# eeZeeRGB.net
KiCad netlist of a schematic drawn in EAGLE
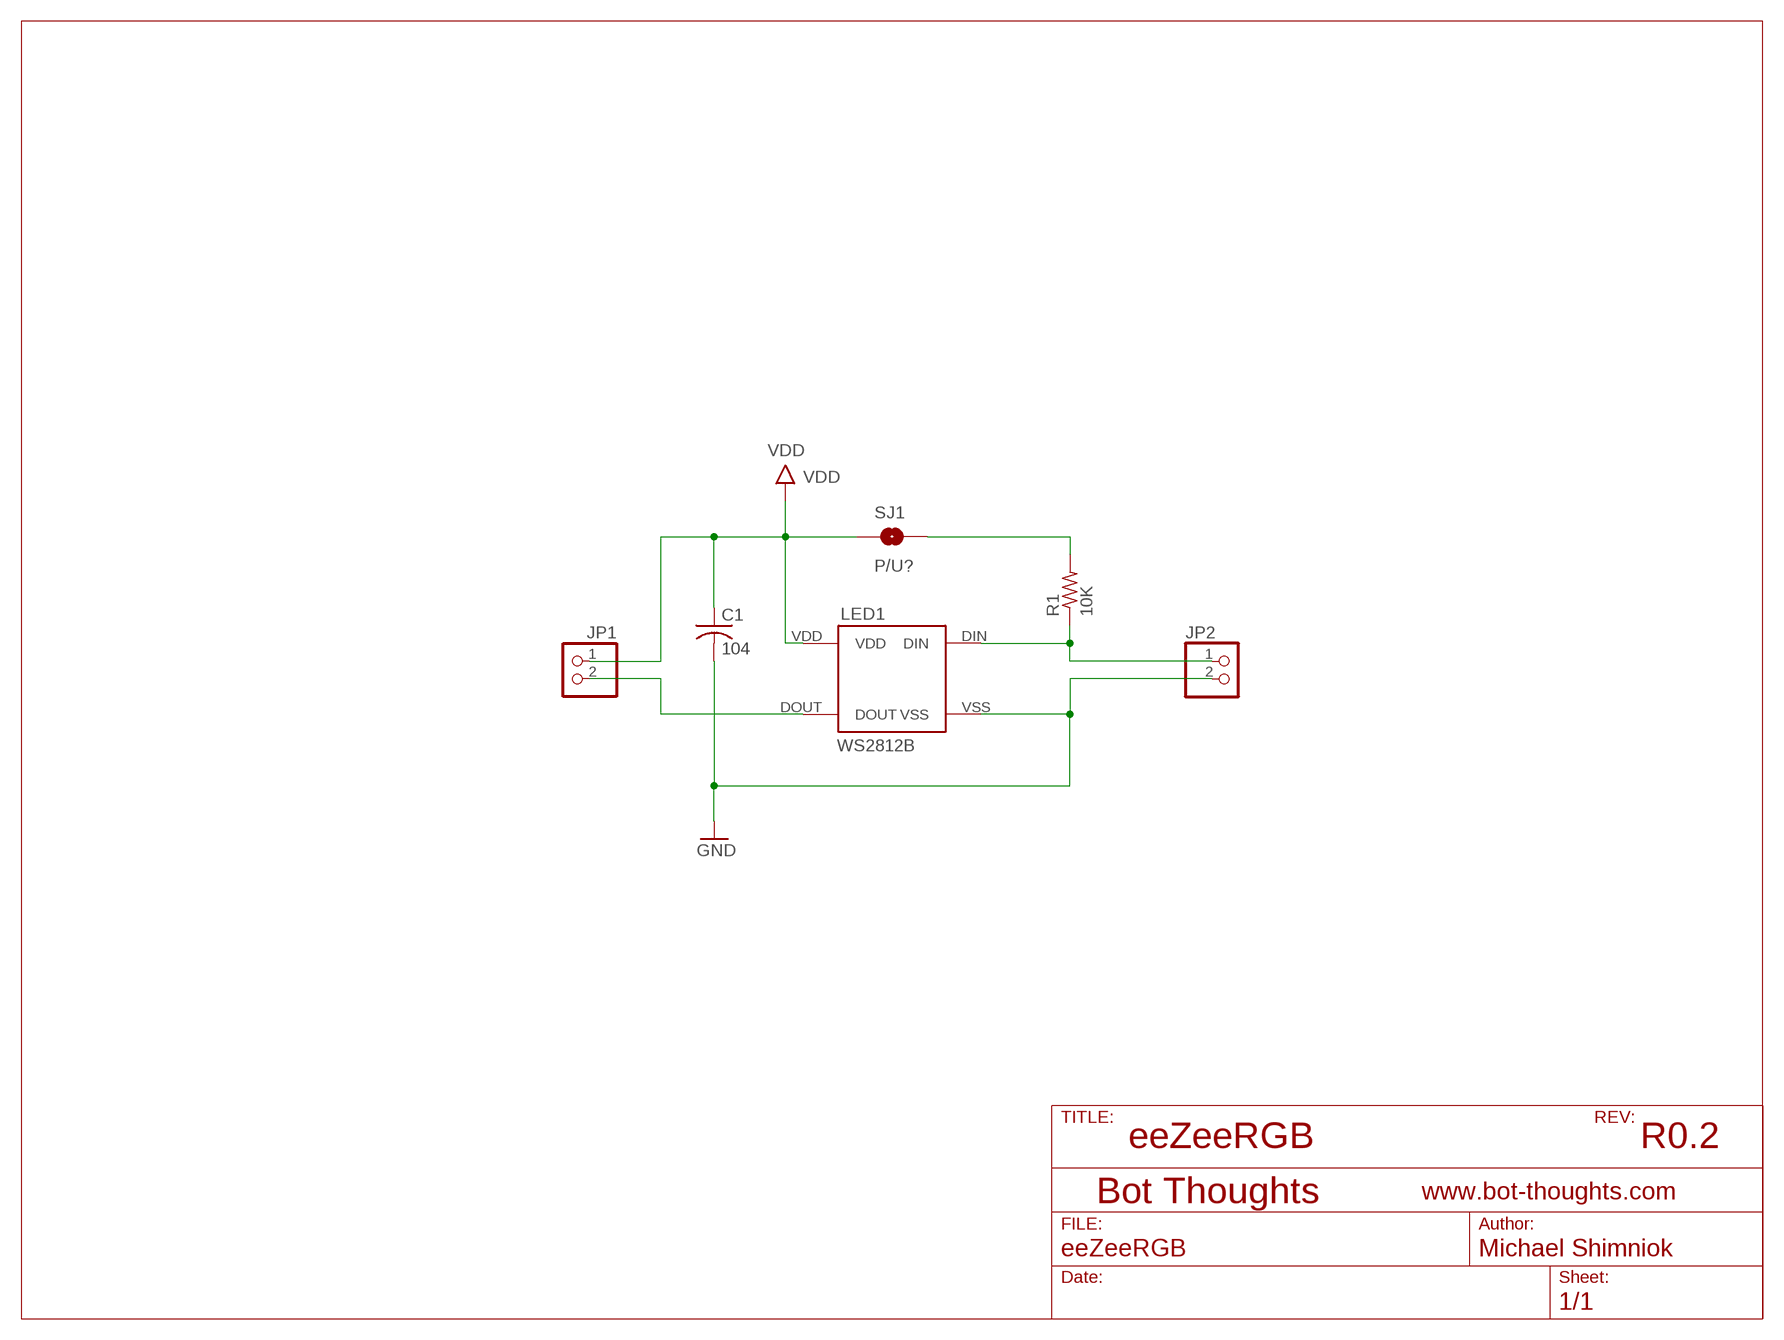
[diagram p0: schematic, sheet 1]

(export (version "E")
  (design (tool "Eeschema 10.0.6"))
  (components
    (comp (ref "C1")
      (value "104")
      (footprint "eagle-import:C0603")
      (libsource (lib "eagle-import") (part "C-USC0603"))
    )
    (comp (ref "JP1")
      (value "PINHD-1X02_2.54-S")
      (footprint "eagle-import:1X02-S")
      (libsource (lib "eagle-import") (part "PINHD-1X02_2.54-S"))
    )
    (comp (ref "JP2")
      (value "PINHD-1X02_2.54-S")
      (footprint "eagle-import:1X02-S")
      (libsource (lib "eagle-import") (part "PINHD-1X02_2.54-S"))
    )
    (comp (ref "LED1")
      (value "WS2812B")
      (footprint "eagle-import:WS2812B")
      (libsource (lib "eagle-import") (part "WS2812B"))
    )
    (comp (ref "R1")
      (value "10K")
      (footprint "eagle-import:R0603")
      (libsource (lib "eagle-import") (part "R-US_R0603"))
    )
    (comp (ref "SJ1")
      (value "P/U?")
      (footprint "eagle-import:SJ_2S")
      (libsource (lib "eagle-import") (part "SOLDERJUMPER-OLDNC"))
    )
  )
  (nets
    (net (code "1") (name "GND") (class "Default")
      (node (ref "C1") (pin "2") (pinfunction "2_2") (pintype "passive"))
      (node (ref "JP2") (pin "2") (pinfunction "2_2") (pintype "passive"))
      (node (ref "LED1") (pin "VSS") (pinfunction "VSS_VSS") (pintype "bidirectional"))
    )
    (net (code "2") (name "Net-(JP1-Pad2)") (class "Default")
      (node (ref "JP1") (pin "2") (pinfunction "2_2") (pintype "passive"))
      (node (ref "LED1") (pin "DOUT") (pinfunction "DOUT_DOUT") (pintype "bidirectional"))
    )
    (net (code "3") (name "Net-(JP2-Pad1)") (class "Default")
      (node (ref "JP2") (pin "1") (pinfunction "1_1") (pintype "passive"))
      (node (ref "LED1") (pin "DIN") (pinfunction "DIN_DIN") (pintype "bidirectional"))
      (node (ref "R1") (pin "1") (pinfunction "1_1") (pintype "passive"))
    )
    (net (code "4") (name "Net-(R1-Pad2)") (class "Default")
      (node (ref "R1") (pin "2") (pinfunction "2_2") (pintype "passive"))
      (node (ref "SJ1") (pin "2") (pinfunction "2_2") (pintype "passive"))
    )
    (net (code "5") (name "VDD") (class "Default")
      (node (ref "C1") (pin "1") (pinfunction "1_1") (pintype "passive"))
      (node (ref "JP1") (pin "1") (pinfunction "1_1") (pintype "passive"))
      (node (ref "LED1") (pin "VDD") (pinfunction "VDD_VDD") (pintype "bidirectional"))
      (node (ref "SJ1") (pin "1") (pinfunction "1_1") (pintype "passive"))
    )
  )
)
